# Circuit_Diagram.net
KiCad netlist of a schematic drawn in EAGLE
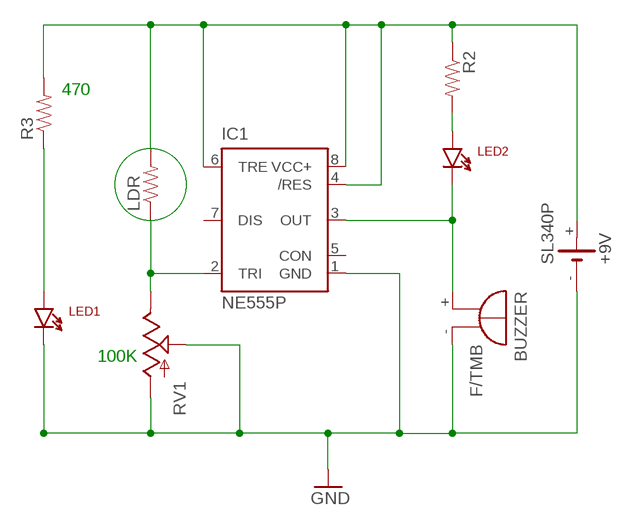
[diagram p0: schematic, sheet 1]

(export (version "E")
  (design (tool "Eeschema 10.0.6"))
  (components
    (comp (ref "+9V")
      (value "SL340P")
      (footprint "eagle-import:SL-340_P3.6V")
      (libsource (lib "eagle-import") (part "SL340P"))
    )
    (comp (ref "BUZZER")
      (value "F/TMB")
      (footprint "eagle-import:F_TMB")
      (libsource (lib "eagle-import") (part "F/TMB"))
    )
    (comp (ref "IC1")
      (value "NE555P")
      (footprint "eagle-import:DIL-08")
      (fields (field (name "MF") "Arrow Electronics") (field (name "MPN") "NE555N"))
      (libsource (lib "eagle-import") (part "NE555P"))
    )
    (comp (ref "LDR")
      (value "RESISTORAXIAL-0.3")
      (footprint "eagle-import:AXIAL-0.3")
      (libsource (lib "eagle-import") (part "RESISTORAXIAL-0.3"))
    )
    (comp (ref "LED1")
      (value "LTE-302")
      (footprint "eagle-import:LTE-302")
      (libsource (lib "eagle-import") (part "LTE-302"))
    )
    (comp (ref "LED2")
      (value "LTE-302")
      (footprint "eagle-import:LTE-302")
      (libsource (lib "eagle-import") (part "LTE-302"))
    )
    (comp (ref "R2")
      (value "RESISTORAXIAL-0.3")
      (footprint "eagle-import:AXIAL-0.3")
      (libsource (lib "eagle-import") (part "RESISTORAXIAL-0.3"))
    )
    (comp (ref "R3")
      (value "RESISTORAXIAL-0.3")
      (footprint "eagle-import:AXIAL-0.3")
      (libsource (lib "eagle-import") (part "RESISTORAXIAL-0.3"))
    )
    (comp (ref "RV1")
      (value "POTTRIM")
      (footprint "eagle-import:TRIM_POT")
      (libsource (lib "eagle-import") (part "POTTRIM"))
    )
  )
  (nets
    (net (code "1") (name "GND") (class "Default")
      (node (ref "+9V") (pin "-") (pinfunction "-_-") (pintype "passive"))
      (node (ref "BUZZER") (pin "-") (pinfunction "-_-") (pintype "passive"))
      (node (ref "IC1") (pin "1") (pinfunction "GND_1") (pintype "power_in"))
      (node (ref "LED1") (pin "C") (pinfunction "C_C") (pintype "bidirectional"))
      (node (ref "RV1") (pin "1") (pinfunction "S_1") (pintype "passive"))
      (node (ref "RV1") (pin "3") (pinfunction "A_3") (pintype "passive"))
    )
    (net (code "2") (name "Net-(IC1-OUT)") (class "Default")
      (node (ref "BUZZER") (pin "+") (pinfunction "+_+") (pintype "passive"))
      (node (ref "IC1") (pin "3") (pinfunction "OUT_3") (pintype "output"))
      (node (ref "LED2") (pin "C") (pinfunction "C_C") (pintype "bidirectional"))
    )
    (net (code "3") (name "Net-(IC1-TRE)") (class "Default")
      (node (ref "+9V") (pin "+") (pinfunction "+_+") (pintype "passive"))
      (node (ref "IC1") (pin "4") (pinfunction "/RES_4") (pintype "input"))
      (node (ref "IC1") (pin "6") (pinfunction "TRE_6") (pintype "input"))
      (node (ref "IC1") (pin "8") (pinfunction "VCC+_8") (pintype "power_in"))
      (node (ref "LDR") (pin "P$2") (pinfunction "2_P$2") (pintype "passive"))
      (node (ref "R2") (pin "P$1") (pinfunction "1_P$1") (pintype "passive"))
      (node (ref "R3") (pin "P$2") (pinfunction "2_P$2") (pintype "passive"))
    )
    (net (code "4") (name "Net-(IC1-TRI)") (class "Default")
      (node (ref "IC1") (pin "2") (pinfunction "TRI_2") (pintype "input"))
      (node (ref "LDR") (pin "P$1") (pinfunction "1_P$1") (pintype "passive"))
      (node (ref "RV1") (pin "2") (pinfunction "E_2") (pintype "passive"))
    )
    (net (code "5") (name "Net-(R2-2)") (class "Default")
      (node (ref "LED2") (pin "A") (pinfunction "A_A") (pintype "bidirectional"))
      (node (ref "R2") (pin "P$2") (pinfunction "2_P$2") (pintype "passive"))
    )
    (net (code "6") (name "Net-(R3-1)") (class "Default")
      (node (ref "LED1") (pin "A") (pinfunction "A_A") (pintype "bidirectional"))
      (node (ref "R3") (pin "P$1") (pinfunction "1_P$1") (pintype "passive"))
    )
    (net (code "7") (name "unconnected-(IC1-CON-Pad5)") (class "Default")
      (node (ref "IC1") (pin "5") (pinfunction "CON_5") (pintype "input"))
    )
    (net (code "8") (name "unconnected-(IC1-DIS-Pad7)") (class "Default")
      (node (ref "IC1") (pin "7") (pinfunction "DIS_7") (pintype "input"))
    )
  )
)
